# ALU.net
KiCad netlist of a schematic drawn in EAGLE
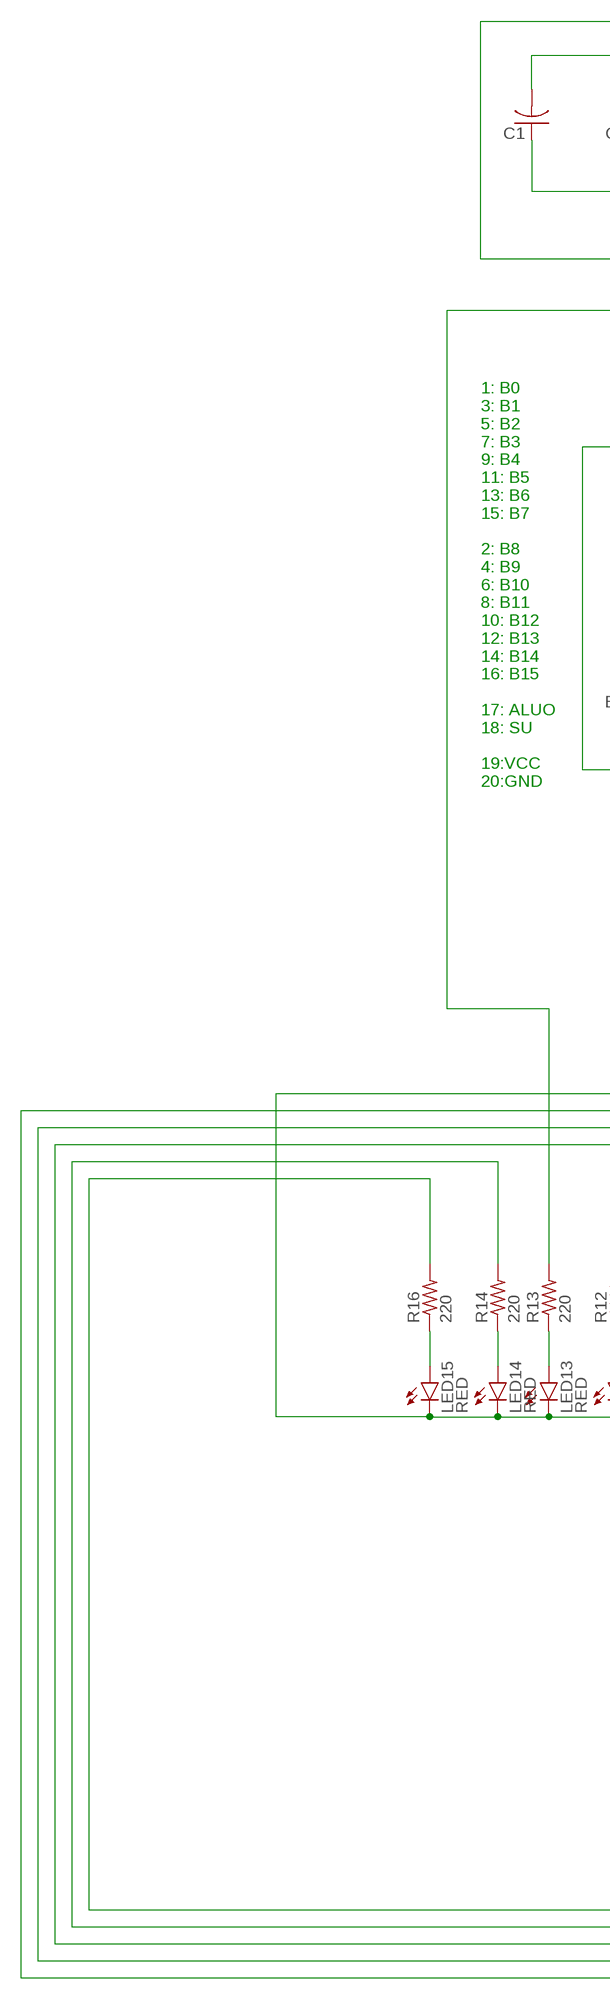
[diagram p0: schematic, sheet 1, part 1 of 2]
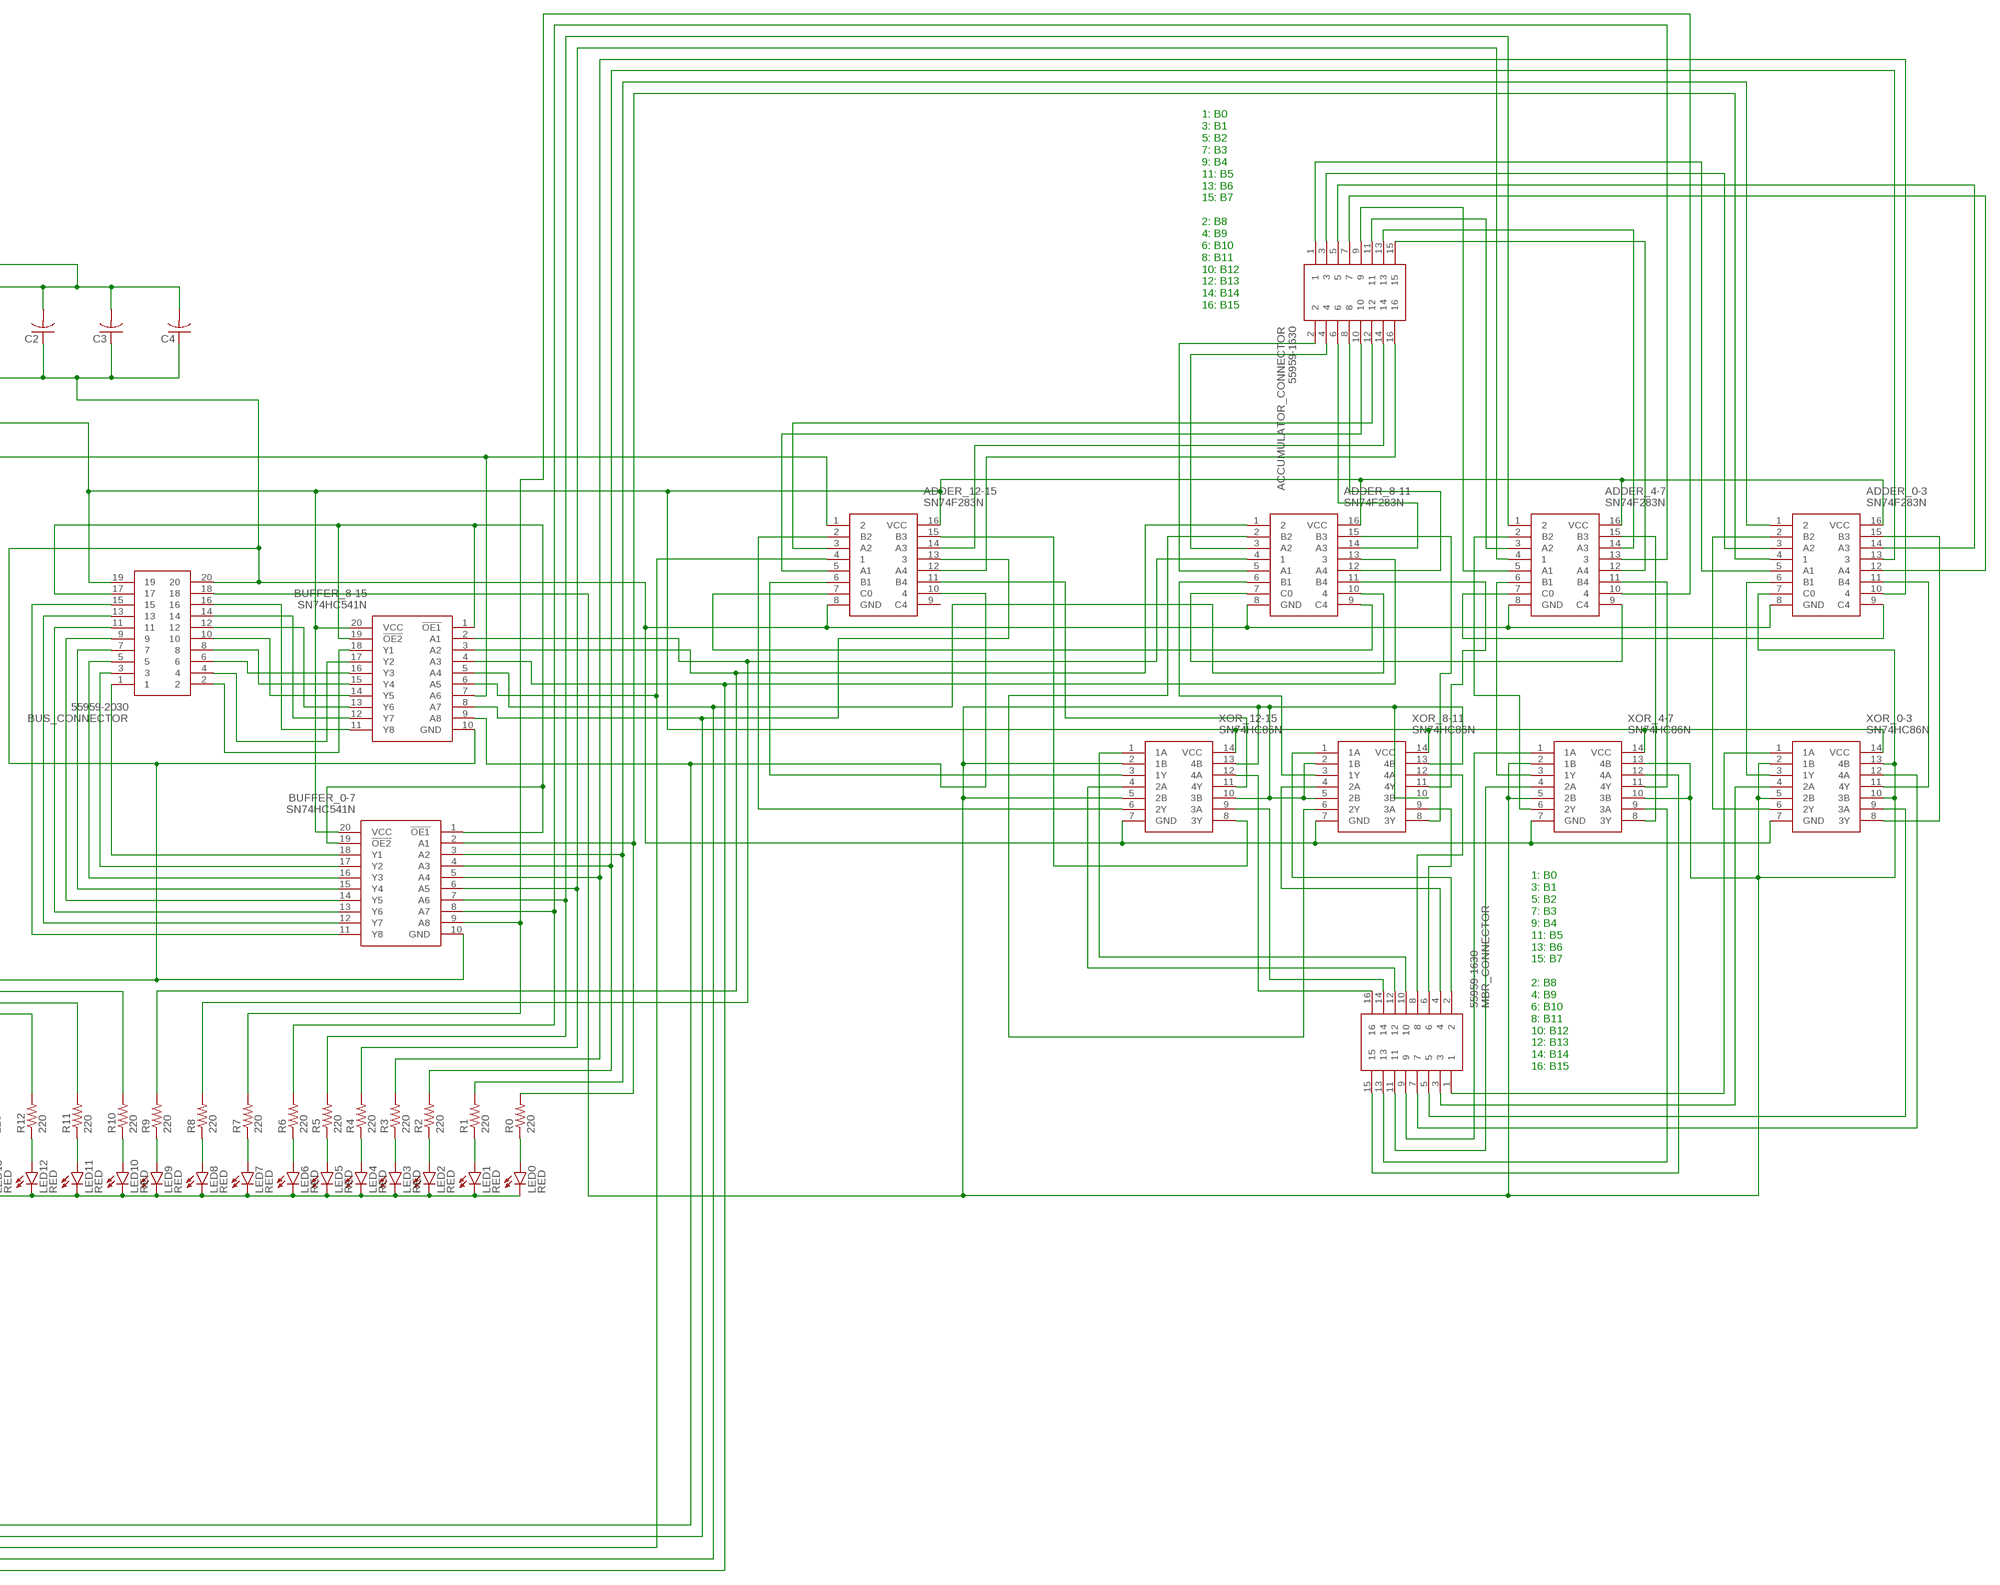
[diagram p1: schematic, sheet 1, part 2 of 2]

(export (version "E")
  (design (tool "Eeschema 10.0.6"))
  (components
    (comp (ref "ACCUMULATOR_CONNECTOR")
      (value "55959-1630")
      (footprint "eagle-import:SHDR16W65P250X200_2X8_1940X140")
      (fields (field (name "MOUSER_PART_NUMBER") "538-55959-1630"))
      (libsource (lib "eagle-import") (part "55959-1630"))
    )
    (comp (ref "ADDER_0-3")
      (value "SN74F283N")
      (footprint "eagle-import:DIP254P762X508-16")
      (fields (field (name "MOUSER_PART_NUMBER") "595-SN74F283N"))
      (libsource (lib "eagle-import") (part "SN74F283N"))
    )
    (comp (ref "ADDER_4-7")
      (value "SN74F283N")
      (footprint "eagle-import:DIP254P762X508-16")
      (fields (field (name "MOUSER_PART_NUMBER") "595-SN74F283N"))
      (libsource (lib "eagle-import") (part "SN74F283N"))
    )
    (comp (ref "ADDER_8-11")
      (value "SN74F283N")
      (footprint "eagle-import:DIP254P762X508-16")
      (fields (field (name "MOUSER_PART_NUMBER") "595-SN74F283N"))
      (libsource (lib "eagle-import") (part "SN74F283N"))
    )
    (comp (ref "ADDER_12-15")
      (value "SN74F283N")
      (footprint "eagle-import:DIP254P762X508-16")
      (fields (field (name "MOUSER_PART_NUMBER") "595-SN74F283N"))
      (libsource (lib "eagle-import") (part "SN74F283N"))
    )
    (comp (ref "BUFFER_0-7")
      (value "SN74HC541N")
      (footprint "eagle-import:DIP794W53P254L2540H508Q20N")
      (fields (field (name "MOUSER_PART_NUMBER") "595-SN74HC541N"))
      (libsource (lib "eagle-import") (part "SN74HC541N"))
    )
    (comp (ref "BUFFER_8-15")
      (value "SN74HC541N")
      (footprint "eagle-import:DIP794W53P254L2540H508Q20N")
      (fields (field (name "MOUSER_PART_NUMBER") "595-SN74HC541N"))
      (libsource (lib "eagle-import") (part "SN74HC541N"))
    )
    (comp (ref "BUS_CONNECTOR")
      (value "55959-2030")
      (footprint "eagle-import:55959-2030_1")
      (fields (field (name "MOUSER_PART_NUMBER") "538-55959-2030"))
      (libsource (lib "eagle-import") (part "55959-2030"))
    )
    (comp (ref "C1")
      (value "C-US025-024X044")
      (footprint "eagle-import:C025-024X044")
      (libsource (lib "eagle-import") (part "C-US025-024X044"))
    )
    (comp (ref "C2")
      (value "C-US025-024X044")
      (footprint "eagle-import:C025-024X044")
      (libsource (lib "eagle-import") (part "C-US025-024X044"))
    )
    (comp (ref "C3")
      (value "C-US025-024X044")
      (footprint "eagle-import:C025-024X044")
      (libsource (lib "eagle-import") (part "C-US025-024X044"))
    )
    (comp (ref "C4")
      (value "C-US025-024X044")
      (footprint "eagle-import:C025-024X044")
      (libsource (lib "eagle-import") (part "C-US025-024X044"))
    )
    (comp (ref "LED0")
      (value "RED")
      (footprint "eagle-import:LED3MM")
      (libsource (lib "eagle-import") (part "LED3MM"))
    )
    (comp (ref "LED1")
      (value "RED")
      (footprint "eagle-import:LED3MM")
      (libsource (lib "eagle-import") (part "LED3MM"))
    )
    (comp (ref "LED2")
      (value "RED")
      (footprint "eagle-import:LED3MM")
      (libsource (lib "eagle-import") (part "LED3MM"))
    )
    (comp (ref "LED3")
      (value "RED")
      (footprint "eagle-import:LED3MM")
      (libsource (lib "eagle-import") (part "LED3MM"))
    )
    (comp (ref "LED4")
      (value "RED")
      (footprint "eagle-import:LED3MM")
      (libsource (lib "eagle-import") (part "LED3MM"))
    )
    (comp (ref "LED5")
      (value "RED")
      (footprint "eagle-import:LED3MM")
      (libsource (lib "eagle-import") (part "LED3MM"))
    )
    (comp (ref "LED6")
      (value "RED")
      (footprint "eagle-import:LED3MM")
      (libsource (lib "eagle-import") (part "LED3MM"))
    )
    (comp (ref "LED7")
      (value "RED")
      (footprint "eagle-import:LED3MM")
      (libsource (lib "eagle-import") (part "LED3MM"))
    )
    (comp (ref "LED8")
      (value "RED")
      (footprint "eagle-import:LED3MM")
      (libsource (lib "eagle-import") (part "LED3MM"))
    )
    (comp (ref "LED9")
      (value "RED")
      (footprint "eagle-import:LED3MM")
      (libsource (lib "eagle-import") (part "LED3MM"))
    )
    (comp (ref "LED10")
      (value "RED")
      (footprint "eagle-import:LED3MM")
      (libsource (lib "eagle-import") (part "LED3MM"))
    )
    (comp (ref "LED11")
      (value "RED")
      (footprint "eagle-import:LED3MM")
      (libsource (lib "eagle-import") (part "LED3MM"))
    )
    (comp (ref "LED12")
      (value "RED")
      (footprint "eagle-import:LED3MM")
      (libsource (lib "eagle-import") (part "LED3MM"))
    )
    (comp (ref "LED13")
      (value "RED")
      (footprint "eagle-import:LED3MM")
      (libsource (lib "eagle-import") (part "LED3MM"))
    )
    (comp (ref "LED14")
      (value "RED")
      (footprint "eagle-import:LED3MM")
      (libsource (lib "eagle-import") (part "LED3MM"))
    )
    (comp (ref "LED15")
      (value "RED")
      (footprint "eagle-import:LED3MM")
      (libsource (lib "eagle-import") (part "LED3MM"))
    )
    (comp (ref "MBR_CONNECTOR")
      (value "55959-1630")
      (footprint "eagle-import:SHDR16W65P250X200_2X8_1940X140")
      (fields (field (name "MOUSER_PART_NUMBER") "538-55959-1630"))
      (libsource (lib "eagle-import") (part "55959-1630"))
    )
    (comp (ref "R0")
      (value "220")
      (footprint "eagle-import:0204_7")
      (libsource (lib "eagle-import") (part "R-US_0204/7"))
    )
    (comp (ref "R1")
      (value "220")
      (footprint "eagle-import:0204_7")
      (libsource (lib "eagle-import") (part "R-US_0204/7"))
    )
    (comp (ref "R2")
      (value "220")
      (footprint "eagle-import:0204_7")
      (libsource (lib "eagle-import") (part "R-US_0204/7"))
    )
    (comp (ref "R3")
      (value "220")
      (footprint "eagle-import:0204_7")
      (libsource (lib "eagle-import") (part "R-US_0204/7"))
    )
    (comp (ref "R4")
      (value "220")
      (footprint "eagle-import:0204_7")
      (libsource (lib "eagle-import") (part "R-US_0204/7"))
    )
    (comp (ref "R5")
      (value "220")
      (footprint "eagle-import:0204_7")
      (libsource (lib "eagle-import") (part "R-US_0204/7"))
    )
    (comp (ref "R6")
      (value "220")
      (footprint "eagle-import:0204_7")
      (libsource (lib "eagle-import") (part "R-US_0204/7"))
    )
    (comp (ref "R7")
      (value "220")
      (footprint "eagle-import:0204_7")
      (libsource (lib "eagle-import") (part "R-US_0204/7"))
    )
    (comp (ref "R8")
      (value "220")
      (footprint "eagle-import:0204_7")
      (libsource (lib "eagle-import") (part "R-US_0204/7"))
    )
    (comp (ref "R9")
      (value "220")
      (footprint "eagle-import:0204_7")
      (libsource (lib "eagle-import") (part "R-US_0204/7"))
    )
    (comp (ref "R10")
      (value "220")
      (footprint "eagle-import:0204_7")
      (libsource (lib "eagle-import") (part "R-US_0204/7"))
    )
    (comp (ref "R11")
      (value "220")
      (footprint "eagle-import:0204_7")
      (libsource (lib "eagle-import") (part "R-US_0204/7"))
    )
    (comp (ref "R12")
      (value "220")
      (footprint "eagle-import:0204_7")
      (libsource (lib "eagle-import") (part "R-US_0204/7"))
    )
    (comp (ref "R13")
      (value "220")
      (footprint "eagle-import:0204_7")
      (libsource (lib "eagle-import") (part "R-US_0204/7"))
    )
    (comp (ref "R14")
      (value "220")
      (footprint "eagle-import:0204_7")
      (libsource (lib "eagle-import") (part "R-US_0204/7"))
    )
    (comp (ref "R16")
      (value "220")
      (footprint "eagle-import:0204_7")
      (libsource (lib "eagle-import") (part "R-US_0204/7"))
    )
    (comp (ref "XOR_0-3")
      (value "SN74HC86N")
      (footprint "eagle-import:DIP794W53P254L1930H508Q14N")
      (fields (field (name "MOUSER_PART_NUMBER") "595-SN74HC86N"))
      (libsource (lib "eagle-import") (part "SN74HC86N"))
    )
    (comp (ref "XOR_4-7")
      (value "SN74HC86N")
      (footprint "eagle-import:DIP794W53P254L1930H508Q14N")
      (fields (field (name "MOUSER_PART_NUMBER") "595-SN74HC86N"))
      (libsource (lib "eagle-import") (part "SN74HC86N"))
    )
    (comp (ref "XOR_8-11")
      (value "SN74HC86N")
      (footprint "eagle-import:DIP794W53P254L1930H508Q14N")
      (fields (field (name "MOUSER_PART_NUMBER") "595-SN74HC86N"))
      (libsource (lib "eagle-import") (part "SN74HC86N"))
    )
    (comp (ref "XOR_12-15")
      (value "SN74HC86N")
      (footprint "eagle-import:DIP794W53P254L1930H508Q14N")
      (fields (field (name "MOUSER_PART_NUMBER") "595-SN74HC86N"))
      (libsource (lib "eagle-import") (part "SN74HC86N"))
    )
  )
  (nets
    (net (code "1") (name "Net-(ADDER_0-3-1)") (class "Default")
      (node (ref "ADDER_0-3") (pin "4") (pinfunction "1_4") (pintype "bidirectional"))
      (node (ref "BUFFER_0-7") (pin "2") (pinfunction "A1_2") (pintype "bidirectional"))
      (node (ref "R0") (pin "2") (pinfunction "2_2") (pintype "passive"))
    )
    (net (code "2") (name "Net-(ADDER_0-3-2)") (class "Default")
      (node (ref "ADDER_0-3") (pin "1") (pinfunction "2_1") (pintype "bidirectional"))
      (node (ref "BUFFER_0-7") (pin "3") (pinfunction "A2_3") (pintype "bidirectional"))
      (node (ref "R1") (pin "2") (pinfunction "2_2") (pintype "passive"))
    )
    (net (code "3") (name "Net-(ADDER_0-3-3)") (class "Default")
      (node (ref "ADDER_0-3") (pin "13") (pinfunction "3_13") (pintype "bidirectional"))
      (node (ref "BUFFER_0-7") (pin "4") (pinfunction "A3_4") (pintype "bidirectional"))
      (node (ref "R2") (pin "2") (pinfunction "2_2") (pintype "passive"))
    )
    (net (code "4") (name "Net-(ADDER_0-3-4)") (class "Default")
      (node (ref "ADDER_0-3") (pin "10") (pinfunction "4_10") (pintype "bidirectional"))
      (node (ref "BUFFER_0-7") (pin "5") (pinfunction "A4_5") (pintype "bidirectional"))
      (node (ref "R3") (pin "2") (pinfunction "2_2") (pintype "passive"))
    )
    (net (code "5") (name "Net-(ADDER_0-3-A1)") (class "Default")
      (node (ref "ACCUMULATOR_CONNECTOR") (pin "1") (pinfunction "1_1") (pintype "bidirectional"))
      (node (ref "ADDER_0-3") (pin "5") (pinfunction "A1_5") (pintype "bidirectional"))
    )
    (net (code "6") (name "Net-(ADDER_0-3-A2)") (class "Default")
      (node (ref "ACCUMULATOR_CONNECTOR") (pin "3") (pinfunction "3_3") (pintype "bidirectional"))
      (node (ref "ADDER_0-3") (pin "3") (pinfunction "A2_3") (pintype "bidirectional"))
    )
    (net (code "7") (name "Net-(ADDER_0-3-A3)") (class "Default")
      (node (ref "ACCUMULATOR_CONNECTOR") (pin "5") (pinfunction "5_5") (pintype "bidirectional"))
      (node (ref "ADDER_0-3") (pin "14") (pinfunction "A3_14") (pintype "bidirectional"))
    )
    (net (code "8") (name "Net-(ADDER_0-3-A4)") (class "Default")
      (node (ref "ACCUMULATOR_CONNECTOR") (pin "7") (pinfunction "7_7") (pintype "bidirectional"))
      (node (ref "ADDER_0-3") (pin "12") (pinfunction "A4_12") (pintype "bidirectional"))
    )
    (net (code "9") (name "Net-(ADDER_0-3-B1)") (class "Default")
      (node (ref "ADDER_0-3") (pin "6") (pinfunction "B1_6") (pintype "bidirectional"))
      (node (ref "XOR_0-3") (pin "3") (pinfunction "1Y_3") (pintype "bidirectional"))
    )
    (net (code "10") (name "Net-(ADDER_0-3-B2)") (class "Default")
      (node (ref "ADDER_0-3") (pin "2") (pinfunction "B2_2") (pintype "bidirectional"))
      (node (ref "XOR_0-3") (pin "6") (pinfunction "2Y_6") (pintype "bidirectional"))
    )
    (net (code "11") (name "Net-(ADDER_0-3-B3)") (class "Default")
      (node (ref "ADDER_0-3") (pin "15") (pinfunction "B3_15") (pintype "bidirectional"))
      (node (ref "XOR_0-3") (pin "8") (pinfunction "3Y_8") (pintype "bidirectional"))
    )
    (net (code "12") (name "Net-(ADDER_0-3-B4)") (class "Default")
      (node (ref "ADDER_0-3") (pin "11") (pinfunction "B4_11") (pintype "bidirectional"))
      (node (ref "XOR_0-3") (pin "11") (pinfunction "4Y_11") (pintype "bidirectional"))
    )
    (net (code "13") (name "Net-(ADDER_0-3-C0)") (class "Default")
      (node (ref "ADDER_0-3") (pin "7") (pinfunction "C0_7") (pintype "bidirectional"))
      (node (ref "BUS_CONNECTOR") (pin "18") (pinfunction "18_18") (pintype "bidirectional"))
      (node (ref "XOR_0-3") (pin "10") (pinfunction "3B_10") (pintype "bidirectional"))
      (node (ref "XOR_0-3") (pin "13") (pinfunction "4B_13") (pintype "bidirectional"))
      (node (ref "XOR_0-3") (pin "2") (pinfunction "1B_2") (pintype "bidirectional"))
      (node (ref "XOR_0-3") (pin "5") (pinfunction "2B_5") (pintype "bidirectional"))
      (node (ref "XOR_12-15") (pin "10") (pinfunction "3B_10") (pintype "bidirectional"))
      (node (ref "XOR_12-15") (pin "13") (pinfunction "4B_13") (pintype "bidirectional"))
      (node (ref "XOR_12-15") (pin "2") (pinfunction "1B_2") (pintype "bidirectional"))
      (node (ref "XOR_12-15") (pin "5") (pinfunction "2B_5") (pintype "bidirectional"))
      (node (ref "XOR_4-7") (pin "10") (pinfunction "3B_10") (pintype "bidirectional"))
      (node (ref "XOR_4-7") (pin "13") (pinfunction "4B_13") (pintype "bidirectional"))
      (node (ref "XOR_4-7") (pin "2") (pinfunction "1B_2") (pintype "bidirectional"))
      (node (ref "XOR_4-7") (pin "5") (pinfunction "2B_5") (pintype "bidirectional"))
      (node (ref "XOR_8-11") (pin "10") (pinfunction "3B_10") (pintype "bidirectional"))
      (node (ref "XOR_8-11") (pin "13") (pinfunction "4B_13") (pintype "bidirectional"))
      (node (ref "XOR_8-11") (pin "2") (pinfunction "1B_2") (pintype "bidirectional"))
      (node (ref "XOR_8-11") (pin "5") (pinfunction "2B_5") (pintype "bidirectional"))
    )
    (net (code "14") (name "Net-(ADDER_0-3-C4)") (class "Default")
      (node (ref "ADDER_0-3") (pin "9") (pinfunction "C4_9") (pintype "bidirectional"))
      (node (ref "ADDER_4-7") (pin "7") (pinfunction "C0_7") (pintype "bidirectional"))
    )
    (net (code "15") (name "Net-(ADDER_0-3-GND)") (class "Default")
      (node (ref "ADDER_0-3") (pin "8") (pinfunction "GND_8") (pintype "bidirectional"))
      (node (ref "ADDER_12-15") (pin "8") (pinfunction "GND_8") (pintype "bidirectional"))
      (node (ref "ADDER_4-7") (pin "8") (pinfunction "GND_8") (pintype "bidirectional"))
      (node (ref "ADDER_8-11") (pin "8") (pinfunction "GND_8") (pintype "bidirectional"))
      (node (ref "BUFFER_0-7") (pin "10") (pinfunction "GND_10") (pintype "bidirectional"))
      (node (ref "BUFFER_8-15") (pin "10") (pinfunction "GND_10") (pintype "bidirectional"))
      (node (ref "BUS_CONNECTOR") (pin "20") (pinfunction "20_20") (pintype "bidirectional"))
      (node (ref "C1") (pin "1") (pinfunction "1_1") (pintype "passive"))
      (node (ref "C2") (pin "1") (pinfunction "1_1") (pintype "passive"))
      (node (ref "C3") (pin "1") (pinfunction "1_1") (pintype "passive"))
      (node (ref "C4") (pin "1") (pinfunction "1_1") (pintype "passive"))
      (node (ref "LED0") (pin "K") (pinfunction "C_K") (pintype "passive"))
      (node (ref "LED1") (pin "K") (pinfunction "C_K") (pintype "passive"))
      (node (ref "LED10") (pin "K") (pinfunction "C_K") (pintype "passive"))
      (node (ref "LED11") (pin "K") (pinfunction "C_K") (pintype "passive"))
      (node (ref "LED12") (pin "K") (pinfunction "C_K") (pintype "passive"))
      (node (ref "LED13") (pin "K") (pinfunction "C_K") (pintype "passive"))
      (node (ref "LED14") (pin "K") (pinfunction "C_K") (pintype "passive"))
      (node (ref "LED15") (pin "K") (pinfunction "C_K") (pintype "passive"))
      (node (ref "LED2") (pin "K") (pinfunction "C_K") (pintype "passive"))
      (node (ref "LED3") (pin "K") (pinfunction "C_K") (pintype "passive"))
      (node (ref "LED4") (pin "K") (pinfunction "C_K") (pintype "passive"))
      (node (ref "LED5") (pin "K") (pinfunction "C_K") (pintype "passive"))
      (node (ref "LED6") (pin "K") (pinfunction "C_K") (pintype "passive"))
      (node (ref "LED7") (pin "K") (pinfunction "C_K") (pintype "passive"))
      (node (ref "LED8") (pin "K") (pinfunction "C_K") (pintype "passive"))
      (node (ref "LED9") (pin "K") (pinfunction "C_K") (pintype "passive"))
      (node (ref "XOR_0-3") (pin "7") (pinfunction "GND_7") (pintype "bidirectional"))
      (node (ref "XOR_12-15") (pin "7") (pinfunction "GND_7") (pintype "bidirectional"))
      (node (ref "XOR_4-7") (pin "7") (pinfunction "GND_7") (pintype "bidirectional"))
      (node (ref "XOR_8-11") (pin "7") (pinfunction "GND_7") (pintype "bidirectional"))
    )
    (net (code "16") (name "Net-(ADDER_0-3-VCC)") (class "Default")
      (node (ref "ADDER_0-3") (pin "16") (pinfunction "VCC_16") (pintype "bidirectional"))
      (node (ref "ADDER_12-15") (pin "16") (pinfunction "VCC_16") (pintype "bidirectional"))
      (node (ref "ADDER_4-7") (pin "16") (pinfunction "VCC_16") (pintype "bidirectional"))
      (node (ref "ADDER_8-11") (pin "16") (pinfunction "VCC_16") (pintype "bidirectional"))
      (node (ref "BUFFER_0-7") (pin "20") (pinfunction "VCC_20") (pintype "bidirectional"))
      (node (ref "BUFFER_8-15") (pin "20") (pinfunction "VCC_20") (pintype "bidirectional"))
      (node (ref "BUS_CONNECTOR") (pin "19") (pinfunction "19_19") (pintype "bidirectional"))
      (node (ref "C1") (pin "2") (pinfunction "2_2") (pintype "passive"))
      (node (ref "C2") (pin "2") (pinfunction "2_2") (pintype "passive"))
      (node (ref "C3") (pin "2") (pinfunction "2_2") (pintype "passive"))
      (node (ref "C4") (pin "2") (pinfunction "2_2") (pintype "passive"))
      (node (ref "XOR_0-3") (pin "14") (pinfunction "VCC_14") (pintype "bidirectional"))
      (node (ref "XOR_12-15") (pin "14") (pinfunction "VCC_14") (pintype "bidirectional"))
      (node (ref "XOR_4-7") (pin "14") (pinfunction "VCC_14") (pintype "bidirectional"))
      (node (ref "XOR_8-11") (pin "14") (pinfunction "VCC_14") (pintype "bidirectional"))
    )
    (net (code "17") (name "Net-(ADDER_4-7-1)") (class "Default")
      (node (ref "ADDER_4-7") (pin "4") (pinfunction "1_4") (pintype "bidirectional"))
      (node (ref "BUFFER_0-7") (pin "6") (pinfunction "A5_6") (pintype "bidirectional"))
      (node (ref "R4") (pin "2") (pinfunction "2_2") (pintype "passive"))
    )
    (net (code "18") (name "Net-(ADDER_4-7-2)") (class "Default")
      (node (ref "ADDER_4-7") (pin "1") (pinfunction "2_1") (pintype "bidirectional"))
      (node (ref "BUFFER_0-7") (pin "7") (pinfunction "A6_7") (pintype "bidirectional"))
      (node (ref "R5") (pin "2") (pinfunction "2_2") (pintype "passive"))
    )
    (net (code "19") (name "Net-(ADDER_4-7-3)") (class "Default")
      (node (ref "ADDER_4-7") (pin "13") (pinfunction "3_13") (pintype "bidirectional"))
      (node (ref "BUFFER_0-7") (pin "8") (pinfunction "A7_8") (pintype "bidirectional"))
      (node (ref "R6") (pin "2") (pinfunction "2_2") (pintype "passive"))
    )
    (net (code "20") (name "Net-(ADDER_4-7-4)") (class "Default")
      (node (ref "ADDER_4-7") (pin "10") (pinfunction "4_10") (pintype "bidirectional"))
      (node (ref "BUFFER_0-7") (pin "9") (pinfunction "A8_9") (pintype "bidirectional"))
      (node (ref "R7") (pin "2") (pinfunction "2_2") (pintype "passive"))
    )
    (net (code "21") (name "Net-(ADDER_4-7-A1)") (class "Default")
      (node (ref "ACCUMULATOR_CONNECTOR") (pin "9") (pinfunction "9_9") (pintype "bidirectional"))
      (node (ref "ADDER_4-7") (pin "5") (pinfunction "A1_5") (pintype "bidirectional"))
    )
    (net (code "22") (name "Net-(ADDER_4-7-A2)") (class "Default")
      (node (ref "ACCUMULATOR_CONNECTOR") (pin "11") (pinfunction "11_11") (pintype "bidirectional"))
      (node (ref "ADDER_4-7") (pin "3") (pinfunction "A2_3") (pintype "bidirectional"))
    )
    (net (code "23") (name "Net-(ADDER_4-7-A3)") (class "Default")
      (node (ref "ACCUMULATOR_CONNECTOR") (pin "13") (pinfunction "13_13") (pintype "bidirectional"))
      (node (ref "ADDER_4-7") (pin "14") (pinfunction "A3_14") (pintype "bidirectional"))
    )
    (net (code "24") (name "Net-(ADDER_4-7-A4)") (class "Default")
      (node (ref "ACCUMULATOR_CONNECTOR") (pin "15") (pinfunction "15_15") (pintype "bidirectional"))
      (node (ref "ADDER_4-7") (pin "12") (pinfunction "A4_12") (pintype "bidirectional"))
    )
    (net (code "25") (name "Net-(ADDER_4-7-B1)") (class "Default")
      (node (ref "ADDER_4-7") (pin "6") (pinfunction "B1_6") (pintype "bidirectional"))
      (node (ref "XOR_4-7") (pin "3") (pinfunction "1Y_3") (pintype "bidirectional"))
    )
    (net (code "26") (name "Net-(ADDER_4-7-B2)") (class "Default")
      (node (ref "ADDER_4-7") (pin "2") (pinfunction "B2_2") (pintype "bidirectional"))
      (node (ref "XOR_4-7") (pin "6") (pinfunction "2Y_6") (pintype "bidirectional"))
    )
    (net (code "27") (name "Net-(ADDER_4-7-B3)") (class "Default")
      (node (ref "ADDER_4-7") (pin "15") (pinfunction "B3_15") (pintype "bidirectional"))
      (node (ref "XOR_4-7") (pin "8") (pinfunction "3Y_8") (pintype "bidirectional"))
    )
    (net (code "28") (name "Net-(ADDER_4-7-B4)") (class "Default")
      (node (ref "ADDER_4-7") (pin "11") (pinfunction "B4_11") (pintype "bidirectional"))
      (node (ref "XOR_4-7") (pin "11") (pinfunction "4Y_11") (pintype "bidirectional"))
    )
    (net (code "29") (name "Net-(ADDER_4-7-C4)") (class "Default")
      (node (ref "ADDER_4-7") (pin "9") (pinfunction "C4_9") (pintype "bidirectional"))
      (node (ref "ADDER_8-11") (pin "7") (pinfunction "C0_7") (pintype "bidirectional"))
    )
    (net (code "30") (name "Net-(ADDER_8-11-1)") (class "Default")
      (node (ref "ADDER_8-11") (pin "4") (pinfunction "1_4") (pintype "bidirectional"))
      (node (ref "BUFFER_8-15") (pin "2") (pinfunction "A1_2") (pintype "bidirectional"))
      (node (ref "R8") (pin "2") (pinfunction "2_2") (pintype "passive"))
    )
    (net (code "31") (name "Net-(ADDER_8-11-2)") (class "Default")
      (node (ref "ADDER_8-11") (pin "1") (pinfunction "2_1") (pintype "bidirectional"))
      (node (ref "BUFFER_8-15") (pin "3") (pinfunction "A2_3") (pintype "bidirectional"))
      (node (ref "R9") (pin "2") (pinfunction "2_2") (pintype "passive"))
    )
    (net (code "32") (name "Net-(ADDER_8-11-3)") (class "Default")
      (node (ref "ADDER_8-11") (pin "13") (pinfunction "3_13") (pintype "bidirectional"))
      (node (ref "BUFFER_8-15") (pin "4") (pinfunction "A3_4") (pintype "bidirectional"))
      (node (ref "R10") (pin "2") (pinfunction "2_2") (pintype "passive"))
    )
    (net (code "33") (name "Net-(ADDER_8-11-4)") (class "Default")
      (node (ref "ADDER_8-11") (pin "10") (pinfunction "4_10") (pintype "bidirectional"))
      (node (ref "BUFFER_8-15") (pin "5") (pinfunction "A4_5") (pintype "bidirectional"))
      (node (ref "R11") (pin "2") (pinfunction "2_2") (pintype "passive"))
    )
    (net (code "34") (name "Net-(ADDER_8-11-A1)") (class "Default")
      (node (ref "ACCUMULATOR_CONNECTOR") (pin "2") (pinfunction "2_2") (pintype "bidirectional"))
      (node (ref "ADDER_8-11") (pin "5") (pinfunction "A1_5") (pintype "bidirectional"))
    )
    (net (code "35") (name "Net-(ADDER_8-11-A2)") (class "Default")
      (node (ref "ACCUMULATOR_CONNECTOR") (pin "4") (pinfunction "4_4") (pintype "bidirectional"))
      (node (ref "ADDER_8-11") (pin "3") (pinfunction "A2_3") (pintype "bidirectional"))
    )
    (net (code "36") (name "Net-(ADDER_8-11-A3)") (class "Default")
      (node (ref "ACCUMULATOR_CONNECTOR") (pin "6") (pinfunction "6_6") (pintype "bidirectional"))
      (node (ref "ADDER_8-11") (pin "14") (pinfunction "A3_14") (pintype "bidirectional"))
    )
    (net (code "37") (name "Net-(ADDER_8-11-A4)") (class "Default")
      (node (ref "ACCUMULATOR_CONNECTOR") (pin "8") (pinfunction "8_8") (pintype "bidirectional"))
      (node (ref "ADDER_8-11") (pin "12") (pinfunction "A4_12") (pintype "bidirectional"))
    )
    (net (code "38") (name "Net-(ADDER_8-11-B1)") (class "Default")
      (node (ref "ADDER_8-11") (pin "6") (pinfunction "B1_6") (pintype "bidirectional"))
      (node (ref "XOR_8-11") (pin "3") (pinfunction "1Y_3") (pintype "bidirectional"))
    )
    (net (code "39") (name "Net-(ADDER_8-11-B2)") (class "Default")
      (node (ref "ADDER_8-11") (pin "2") (pinfunction "B2_2") (pintype "bidirectional"))
      (node (ref "XOR_8-11") (pin "6") (pinfunction "2Y_6") (pintype "bidirectional"))
    )
    (net (code "40") (name "Net-(ADDER_8-11-B3)") (class "Default")
      (node (ref "ADDER_8-11") (pin "15") (pinfunction "B3_15") (pintype "bidirectional"))
      (node (ref "XOR_8-11") (pin "8") (pinfunction "3Y_8") (pintype "bidirectional"))
    )
    (net (code "41") (name "Net-(ADDER_8-11-B4)") (class "Default")
      (node (ref "ADDER_8-11") (pin "11") (pinfunction "B4_11") (pintype "bidirectional"))
      (node (ref "XOR_8-11") (pin "11") (pinfunction "4Y_11") (pintype "bidirectional"))
    )
    (net (code "42") (name "Net-(ADDER_12-15-1)") (class "Default")
      (node (ref "ADDER_12-15") (pin "4") (pinfunction "1_4") (pintype "bidirectional"))
      (node (ref "BUFFER_8-15") (pin "6") (pinfunction "A5_6") (pintype "bidirectional"))
      (node (ref "R12") (pin "2") (pinfunction "2_2") (pintype "passive"))
    )
    (net (code "43") (name "Net-(ADDER_12-15-2)") (class "Default")
      (node (ref "ADDER_12-15") (pin "1") (pinfunction "2_1") (pintype "bidirectional"))
      (node (ref "BUFFER_8-15") (pin "7") (pinfunction "A6_7") (pintype "bidirectional"))
      (node (ref "R13") (pin "2") (pinfunction "2_2") (pintype "passive"))
    )
    (net (code "44") (name "Net-(ADDER_12-15-3)") (class "Default")
      (node (ref "ADDER_12-15") (pin "13") (pinfunction "3_13") (pintype "bidirectional"))
      (node (ref "BUFFER_8-15") (pin "8") (pinfunction "A7_8") (pintype "bidirectional"))
      (node (ref "R14") (pin "2") (pinfunction "2_2") (pintype "passive"))
    )
    (net (code "45") (name "Net-(ADDER_12-15-4)") (class "Default")
      (node (ref "ADDER_12-15") (pin "10") (pinfunction "4_10") (pintype "bidirectional"))
      (node (ref "BUFFER_8-15") (pin "9") (pinfunction "A8_9") (pintype "bidirectional"))
      (node (ref "R16") (pin "2") (pinfunction "2_2") (pintype "passive"))
    )
    (net (code "46") (name "Net-(ADDER_12-15-A1)") (class "Default")
      (node (ref "ACCUMULATOR_CONNECTOR") (pin "10") (pinfunction "10_10") (pintype "bidirectional"))
      (node (ref "ADDER_12-15") (pin "5") (pinfunction "A1_5") (pintype "bidirectional"))
    )
    (net (code "47") (name "Net-(ADDER_12-15-A2)") (class "Default")
      (node (ref "ACCUMULATOR_CONNECTOR") (pin "12") (pinfunction "12_12") (pintype "bidirectional"))
      (node (ref "ADDER_12-15") (pin "3") (pinfunction "A2_3") (pintype "bidirectional"))
    )
    (net (code "48") (name "Net-(ADDER_12-15-A3)") (class "Default")
      (node (ref "ACCUMULATOR_CONNECTOR") (pin "14") (pinfunction "14_14") (pintype "bidirectional"))
      (node (ref "ADDER_12-15") (pin "14") (pinfunction "A3_14") (pintype "bidirectional"))
    )
    (net (code "49") (name "Net-(ADDER_12-15-A4)") (class "Default")
      (node (ref "ACCUMULATOR_CONNECTOR") (pin "16") (pinfunction "16_16") (pintype "bidirectional"))
      (node (ref "ADDER_12-15") (pin "12") (pinfunction "A4_12") (pintype "bidirectional"))
    )
    (net (code "50") (name "Net-(ADDER_12-15-B1)") (class "Default")
      (node (ref "ADDER_12-15") (pin "6") (pinfunction "B1_6") (pintype "bidirectional"))
      (node (ref "XOR_12-15") (pin "3") (pinfunction "1Y_3") (pintype "bidirectional"))
    )
    (net (code "51") (name "Net-(ADDER_12-15-B2)") (class "Default")
      (node (ref "ADDER_12-15") (pin "2") (pinfunction "B2_2") (pintype "bidirectional"))
      (node (ref "XOR_12-15") (pin "6") (pinfunction "2Y_6") (pintype "bidirectional"))
    )
    (net (code "52") (name "Net-(ADDER_12-15-B3)") (class "Default")
      (node (ref "ADDER_12-15") (pin "15") (pinfunction "B3_15") (pintype "bidirectional"))
      (node (ref "XOR_12-15") (pin "8") (pinfunction "3Y_8") (pintype "bidirectional"))
    )
    (net (code "53") (name "Net-(ADDER_12-15-B4)") (class "Default")
      (node (ref "ADDER_12-15") (pin "11") (pinfunction "B4_11") (pintype "bidirectional"))
      (node (ref "XOR_12-15") (pin "11") (pinfunction "4Y_11") (pintype "bidirectional"))
    )
    (net (code "54") (name "Net-(ADDER_12-15-C0)") (class "Default")
      (node (ref "ADDER_12-15") (pin "7") (pinfunction "C0_7") (pintype "bidirectional"))
      (node (ref "ADDER_8-11") (pin "9") (pinfunction "C4_9") (pintype "bidirectional"))
    )
    (net (code "55") (name "Net-(BUFFER_0-7-Y1)") (class "Default")
      (node (ref "BUFFER_0-7") (pin "18") (pinfunction "Y1_18") (pintype "bidirectional"))
      (node (ref "BUS_CONNECTOR") (pin "1") (pinfunction "1_1") (pintype "bidirectional"))
    )
    (net (code "56") (name "Net-(BUFFER_0-7-Y2)") (class "Default")
      (node (ref "BUFFER_0-7") (pin "17") (pinfunction "Y2_17") (pintype "bidirectional"))
      (node (ref "BUS_CONNECTOR") (pin "3") (pinfunction "3_3") (pintype "bidirectional"))
    )
    (net (code "57") (name "Net-(BUFFER_0-7-Y3)") (class "Default")
      (node (ref "BUFFER_0-7") (pin "16") (pinfunction "Y3_16") (pintype "bidirectional"))
      (node (ref "BUS_CONNECTOR") (pin "5") (pinfunction "5_5") (pintype "bidirectional"))
    )
    (net (code "58") (name "Net-(BUFFER_0-7-Y4)") (class "Default")
      (node (ref "BUFFER_0-7") (pin "15") (pinfunction "Y4_15") (pintype "bidirectional"))
      (node (ref "BUS_CONNECTOR") (pin "7") (pinfunction "7_7") (pintype "bidirectional"))
    )
    (net (code "59") (name "Net-(BUFFER_0-7-Y5)") (class "Default")
      (node (ref "BUFFER_0-7") (pin "14") (pinfunction "Y5_14") (pintype "bidirectional"))
      (node (ref "BUS_CONNECTOR") (pin "9") (pinfunction "9_9") (pintype "bidirectional"))
    )
    (net (code "60") (name "Net-(BUFFER_0-7-Y6)") (class "Default")
      (node (ref "BUFFER_0-7") (pin "13") (pinfunction "Y6_13") (pintype "bidirectional"))
      (node (ref "BUS_CONNECTOR") (pin "11") (pinfunction "11_11") (pintype "bidirectional"))
    )
    (net (code "61") (name "Net-(BUFFER_0-7-Y7)") (class "Default")
      (node (ref "BUFFER_0-7") (pin "12") (pinfunction "Y7_12") (pintype "bidirectional"))
      (node (ref "BUS_CONNECTOR") (pin "13") (pinfunction "13_13") (pintype "bidirectional"))
    )
    (net (code "62") (name "Net-(BUFFER_0-7-Y8)") (class "Default")
      (node (ref "BUFFER_0-7") (pin "11") (pinfunction "Y8_11") (pintype "bidirectional"))
      (node (ref "BUS_CONNECTOR") (pin "15") (pinfunction "15_15") (pintype "bidirectional"))
    )
    (net (code "63") (name "Net-(BUFFER_0-7-~{OE1})") (class "Default")
      (node (ref "BUFFER_0-7") (pin "1") (pinfunction "~{OE1}_1") (pintype "bidirectional"))
      (node (ref "BUFFER_0-7") (pin "19") (pinfunction "~{OE2}_19") (pintype "bidirectional"))
      (node (ref "BUFFER_8-15") (pin "1") (pinfunction "~{OE1}_1") (pintype "bidirectional"))
      (node (ref "BUFFER_8-15") (pin "19") (pinfunction "~{OE2}_19") (pintype "bidirectional"))
      (node (ref "BUS_CONNECTOR") (pin "17") (pinfunction "17_17") (pintype "bidirectional"))
    )
    (net (code "64") (name "Net-(BUFFER_8-15-Y1)") (class "Default")
      (node (ref "BUFFER_8-15") (pin "18") (pinfunction "Y1_18") (pintype "bidirectional"))
      (node (ref "BUS_CONNECTOR") (pin "2") (pinfunction "2_2") (pintype "bidirectional"))
    )
    (net (code "65") (name "Net-(BUFFER_8-15-Y2)") (class "Default")
      (node (ref "BUFFER_8-15") (pin "17") (pinfunction "Y2_17") (pintype "bidirectional"))
      (node (ref "BUS_CONNECTOR") (pin "4") (pinfunction "4_4") (pintype "bidirectional"))
    )
    (net (code "66") (name "Net-(BUFFER_8-15-Y3)") (class "Default")
      (node (ref "BUFFER_8-15") (pin "16") (pinfunction "Y3_16") (pintype "bidirectional"))
      (node (ref "BUS_CONNECTOR") (pin "6") (pinfunction "6_6") (pintype "bidirectional"))
    )
    (net (code "67") (name "Net-(BUFFER_8-15-Y4)") (class "Default")
      (node (ref "BUFFER_8-15") (pin "15") (pinfunction "Y4_15") (pintype "bidirectional"))
      (node (ref "BUS_CONNECTOR") (pin "8") (pinfunction "8_8") (pintype "bidirectional"))
    )
    (net (code "68") (name "Net-(BUFFER_8-15-Y5)") (class "Default")
      (node (ref "BUFFER_8-15") (pin "14") (pinfunction "Y5_14") (pintype "bidirectional"))
      (node (ref "BUS_CONNECTOR") (pin "10") (pinfunction "10_10") (pintype "bidirectional"))
    )
    (net (code "69") (name "Net-(BUFFER_8-15-Y6)") (class "Default")
      (node (ref "BUFFER_8-15") (pin "13") (pinfunction "Y6_13") (pintype "bidirectional"))
      (node (ref "BUS_CONNECTOR") (pin "12") (pinfunction "12_12") (pintype "bidirectional"))
    )
    (net (code "70") (name "Net-(BUFFER_8-15-Y7)") (class "Default")
      (node (ref "BUFFER_8-15") (pin "12") (pinfunction "Y7_12") (pintype "bidirectional"))
      (node (ref "BUS_CONNECTOR") (pin "14") (pinfunction "14_14") (pintype "bidirectional"))
    )
    (net (code "71") (name "Net-(BUFFER_8-15-Y8)") (class "Default")
      (node (ref "BUFFER_8-15") (pin "11") (pinfunction "Y8_11") (pintype "bidirectional"))
      (node (ref "BUS_CONNECTOR") (pin "16") (pinfunction "16_16") (pintype "bidirectional"))
    )
    (net (code "72") (name "Net-(LED0-PadA)") (class "Default")
      (node (ref "LED0") (pin "A") (pinfunction "A_A") (pintype "passive"))
      (node (ref "R0") (pin "1") (pinfunction "1_1") (pintype "passive"))
    )
    (net (code "73") (name "Net-(LED1-PadA)") (class "Default")
      (node (ref "LED1") (pin "A") (pinfunction "A_A") (pintype "passive"))
      (node (ref "R1") (pin "1") (pinfunction "1_1") (pintype "passive"))
    )
    (net (code "74") (name "Net-(LED2-PadA)") (class "Default")
      (node (ref "LED2") (pin "A") (pinfunction "A_A") (pintype "passive"))
      (node (ref "R2") (pin "1") (pinfunction "1_1") (pintype "passive"))
    )
    (net (code "75") (name "Net-(LED3-PadA)") (class "Default")
      (node (ref "LED3") (pin "A") (pinfunction "A_A") (pintype "passive"))
      (node (ref "R3") (pin "1") (pinfunction "1_1") (pintype "passive"))
    )
    (net (code "76") (name "Net-(LED4-PadA)") (class "Default")
      (node (ref "LED4") (pin "A") (pinfunction "A_A") (pintype "passive"))
      (node (ref "R4") (pin "1") (pinfunction "1_1") (pintype "passive"))
    )
    (net (code "77") (name "Net-(LED5-PadA)") (class "Default")
      (node (ref "LED5") (pin "A") (pinfunction "A_A") (pintype "passive"))
      (node (ref "R5") (pin "1") (pinfunction "1_1") (pintype "passive"))
    )
    (net (code "78") (name "Net-(LED6-PadA)") (class "Default")
      (node (ref "LED6") (pin "A") (pinfunction "A_A") (pintype "passive"))
      (node (ref "R6") (pin "1") (pinfunction "1_1") (pintype "passive"))
    )
    (net (code "79") (name "Net-(LED7-PadA)") (class "Default")
      (node (ref "LED7") (pin "A") (pinfunction "A_A") (pintype "passive"))
      (node (ref "R7") (pin "1") (pinfunction "1_1") (pintype "passive"))
    )
    (net (code "80") (name "Net-(LED8-PadA)") (class "Default")
      (node (ref "LED8") (pin "A") (pinfunction "A_A") (pintype "passive"))
      (node (ref "R8") (pin "1") (pinfunction "1_1") (pintype "passive"))
    )
    (net (code "81") (name "Net-(LED9-PadA)") (class "Default")
      (node (ref "LED9") (pin "A") (pinfunction "A_A") (pintype "passive"))
      (node (ref "R9") (pin "1") (pinfunction "1_1") (pintype "passive"))
    )
    (net (code "82") (name "Net-(LED10-PadA)") (class "Default")
      (node (ref "LED10") (pin "A") (pinfunction "A_A") (pintype "passive"))
      (node (ref "R10") (pin "1") (pinfunction "1_1") (pintype "passive"))
    )
    (net (code "83") (name "Net-(LED11-PadA)") (class "Default")
      (node (ref "LED11") (pin "A") (pinfunction "A_A") (pintype "passive"))
      (node (ref "R11") (pin "1") (pinfunction "1_1") (pintype "passive"))
    )
    (net (code "84") (name "Net-(LED12-PadA)") (class "Default")
      (node (ref "LED12") (pin "A") (pinfunction "A_A") (pintype "passive"))
      (node (ref "R12") (pin "1") (pinfunction "1_1") (pintype "passive"))
    )
    (net (code "85") (name "Net-(LED13-PadA)") (class "Default")
      (node (ref "LED13") (pin "A") (pinfunction "A_A") (pintype "passive"))
      (node (ref "R13") (pin "1") (pinfunction "1_1") (pintype "passive"))
    )
    (net (code "86") (name "Net-(LED14-PadA)") (class "Default")
      (node (ref "LED14") (pin "A") (pinfunction "A_A") (pintype "passive"))
      (node (ref "R14") (pin "1") (pinfunction "1_1") (pintype "passive"))
    )
    (net (code "87") (name "Net-(LED15-PadA)") (class "Default")
      (node (ref "LED15") (pin "A") (pinfunction "A_A") (pintype "passive"))
      (node (ref "R16") (pin "1") (pinfunction "1_1") (pintype "passive"))
    )
    (net (code "88") (name "Net-(XOR_0-3-1A)") (class "Default")
      (node (ref "MBR_CONNECTOR") (pin "1") (pinfunction "1_1") (pintype "bidirectional"))
      (node (ref "XOR_0-3") (pin "1") (pinfunction "1A_1") (pintype "bidirectional"))
    )
    (net (code "89") (name "Net-(XOR_0-3-2A)") (class "Default")
      (node (ref "MBR_CONNECTOR") (pin "3") (pinfunction "3_3") (pintype "bidirectional"))
      (node (ref "XOR_0-3") (pin "4") (pinfunction "2A_4") (pintype "bidirectional"))
    )
    (net (code "90") (name "Net-(XOR_0-3-3A)") (class "Default")
      (node (ref "MBR_CONNECTOR") (pin "5") (pinfunction "5_5") (pintype "bidirectional"))
      (node (ref "XOR_0-3") (pin "9") (pinfunction "3A_9") (pintype "bidirectional"))
    )
    (net (code "91") (name "Net-(XOR_0-3-4A)") (class "Default")
      (node (ref "MBR_CONNECTOR") (pin "7") (pinfunction "7_7") (pintype "bidirectional"))
      (node (ref "XOR_0-3") (pin "12") (pinfunction "4A_12") (pintype "bidirectional"))
    )
    (net (code "92") (name "Net-(XOR_4-7-1A)") (class "Default")
      (node (ref "MBR_CONNECTOR") (pin "9") (pinfunction "9_9") (pintype "bidirectional"))
      (node (ref "XOR_4-7") (pin "1") (pinfunction "1A_1") (pintype "bidirectional"))
    )
    (net (code "93") (name "Net-(XOR_4-7-2A)") (class "Default")
      (node (ref "MBR_CONNECTOR") (pin "11") (pinfunction "11_11") (pintype "bidirectional"))
      (node (ref "XOR_4-7") (pin "4") (pinfunction "2A_4") (pintype "bidirectional"))
    )
    (net (code "94") (name "Net-(XOR_4-7-3A)") (class "Default")
      (node (ref "MBR_CONNECTOR") (pin "13") (pinfunction "13_13") (pintype "bidirectional"))
      (node (ref "XOR_4-7") (pin "9") (pinfunction "3A_9") (pintype "bidirectional"))
    )
    (net (code "95") (name "Net-(XOR_4-7-4A)") (class "Default")
      (node (ref "MBR_CONNECTOR") (pin "15") (pinfunction "15_15") (pintype "bidirectional"))
      (node (ref "XOR_4-7") (pin "12") (pinfunction "4A_12") (pintype "bidirectional"))
    )
    (net (code "96") (name "Net-(XOR_8-11-1A)") (class "Default")
      (node (ref "MBR_CONNECTOR") (pin "2") (pinfunction "2_2") (pintype "bidirectional"))
      (node (ref "XOR_8-11") (pin "1") (pinfunction "1A_1") (pintype "bidirectional"))
    )
    (net (code "97") (name "Net-(XOR_8-11-2A)") (class "Default")
      (node (ref "MBR_CONNECTOR") (pin "4") (pinfunction "4_4") (pintype "bidirectional"))
      (node (ref "XOR_8-11") (pin "4") (pinfunction "2A_4") (pintype "bidirectional"))
    )
    (net (code "98") (name "Net-(XOR_8-11-3A)") (class "Default")
      (node (ref "MBR_CONNECTOR") (pin "6") (pinfunction "6_6") (pintype "bidirectional"))
      (node (ref "XOR_8-11") (pin "9") (pinfunction "3A_9") (pintype "bidirectional"))
    )
    (net (code "99") (name "Net-(XOR_8-11-4A)") (class "Default")
      (node (ref "MBR_CONNECTOR") (pin "8") (pinfunction "8_8") (pintype "bidirectional"))
      (node (ref "XOR_8-11") (pin "12") (pinfunction "4A_12") (pintype "bidirectional"))
    )
    (net (code "100") (name "Net-(XOR_12-15-1A)") (class "Default")
      (node (ref "MBR_CONNECTOR") (pin "10") (pinfunction "10_10") (pintype "bidirectional"))
      (node (ref "XOR_12-15") (pin "1") (pinfunction "1A_1") (pintype "bidirectional"))
    )
    (net (code "101") (name "Net-(XOR_12-15-2A)") (class "Default")
      (node (ref "MBR_CONNECTOR") (pin "12") (pinfunction "12_12") (pintype "bidirectional"))
      (node (ref "XOR_12-15") (pin "4") (pinfunction "2A_4") (pintype "bidirectional"))
    )
    (net (code "102") (name "Net-(XOR_12-15-3A)") (class "Default")
      (node (ref "MBR_CONNECTOR") (pin "14") (pinfunction "14_14") (pintype "bidirectional"))
      (node (ref "XOR_12-15") (pin "9") (pinfunction "3A_9") (pintype "bidirectional"))
    )
    (net (code "103") (name "Net-(XOR_12-15-4A)") (class "Default")
      (node (ref "MBR_CONNECTOR") (pin "16") (pinfunction "16_16") (pintype "bidirectional"))
      (node (ref "XOR_12-15") (pin "12") (pinfunction "4A_12") (pintype "bidirectional"))
    )
    (net (code "104") (name "unconnected-(ADDER_12-15-C4-Pad9)") (class "Default")
      (node (ref "ADDER_12-15") (pin "9") (pinfunction "C4_9") (pintype "bidirectional"))
    )
  )
)
